# SCH_PianoBoard_P3_2024-09-13.net
KiCad netlist of a schematic drawn in EasyEDA
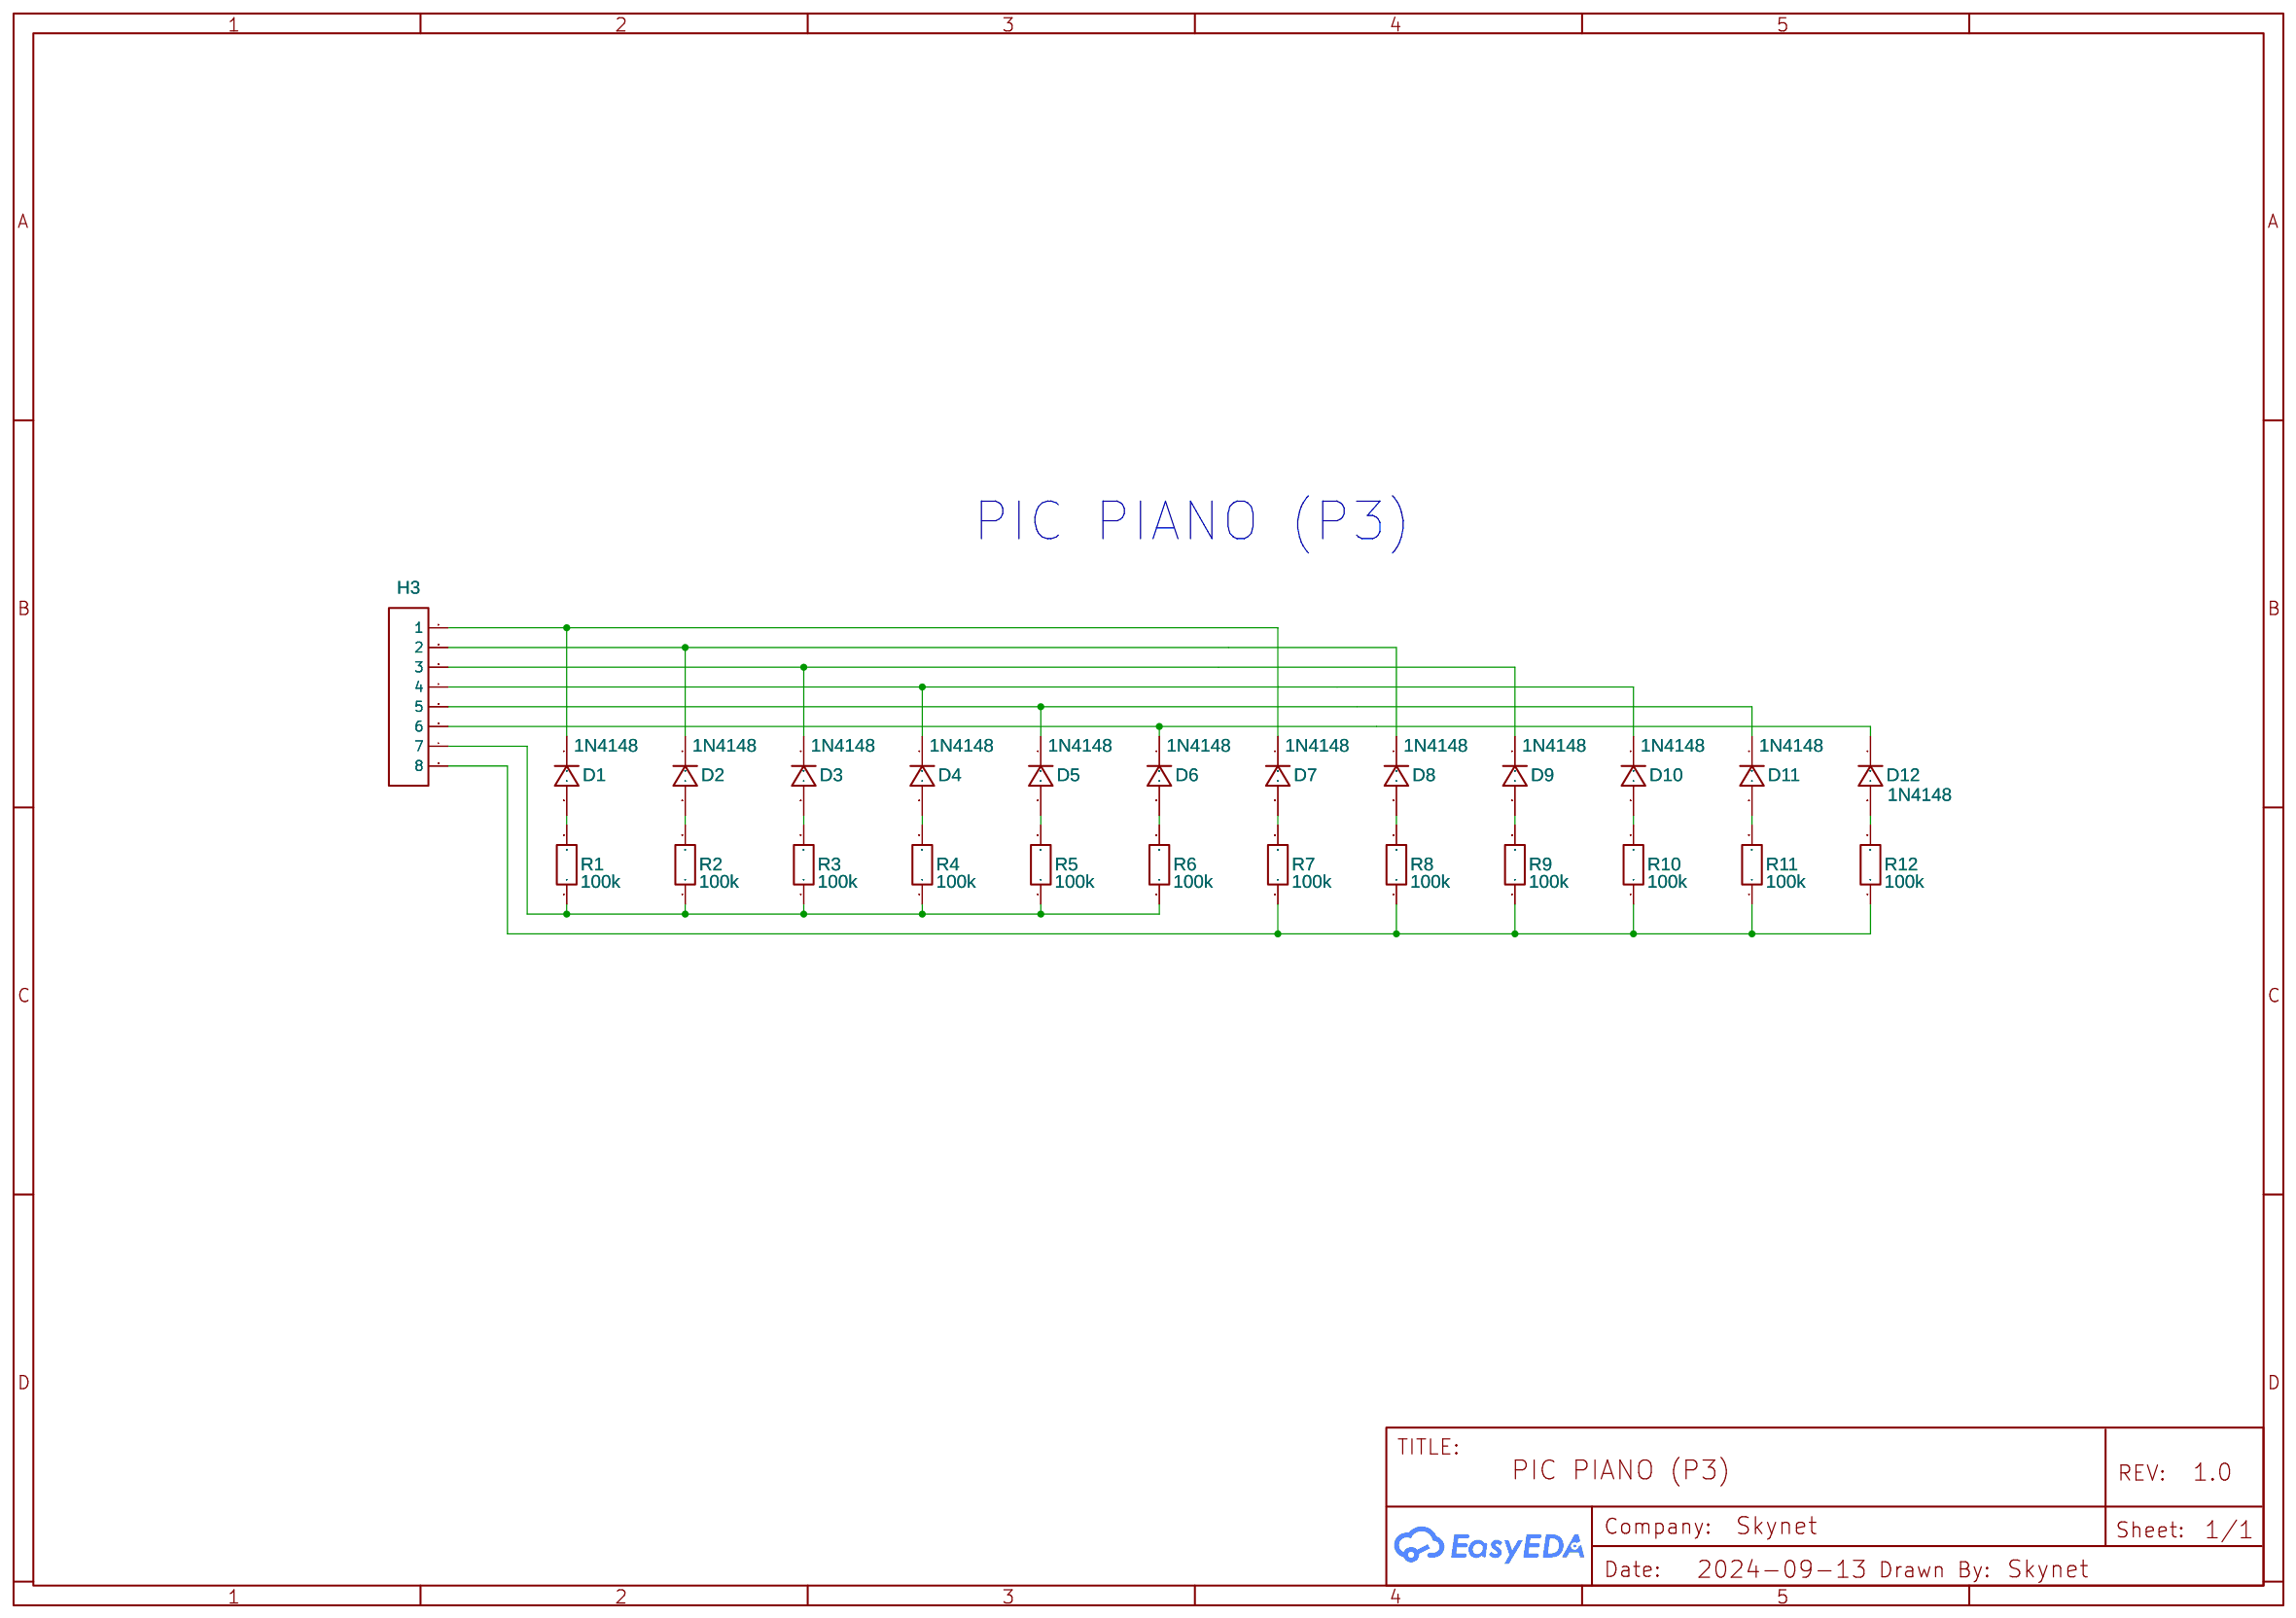
[diagram p0: schematic sheet]

(export (version "E")
  (design (tool "Eeschema 10.0.6"))
  (components
    (comp (ref "D1")
      (value "1N4148")
      (fields (field (name "Manufacturer Part") "1N4148WX-TP") (field (name "Manufacturer") "MCC(美微科)"))
      (libsource (lib "") (part "1N4148WX-TP"))
    )
    (comp (ref "D2")
      (value "1N4148")
      (fields (field (name "Manufacturer Part") "1N4148WX-TP") (field (name "Manufacturer") "MCC(美微科)"))
      (libsource (lib "") (part "1N4148WX-TP"))
    )
    (comp (ref "D3")
      (value "1N4148")
      (fields (field (name "Manufacturer Part") "1N4148WX-TP") (field (name "Manufacturer") "MCC(美微科)"))
      (libsource (lib "") (part "1N4148WX-TP"))
    )
    (comp (ref "D4")
      (value "1N4148")
      (fields (field (name "Manufacturer Part") "1N4148WX-TP") (field (name "Manufacturer") "MCC(美微科)"))
      (libsource (lib "") (part "1N4148WX-TP"))
    )
    (comp (ref "D5")
      (value "1N4148")
      (fields (field (name "Manufacturer Part") "1N4148WX-TP") (field (name "Manufacturer") "MCC(美微科)"))
      (libsource (lib "") (part "1N4148WX-TP"))
    )
    (comp (ref "D6")
      (value "1N4148")
      (fields (field (name "Manufacturer Part") "1N4148WX-TP") (field (name "Manufacturer") "MCC(美微科)"))
      (libsource (lib "") (part "1N4148WX-TP"))
    )
    (comp (ref "D7")
      (value "1N4148")
      (fields (field (name "Manufacturer Part") "1N4148WX-TP") (field (name "Manufacturer") "MCC(美微科)"))
      (libsource (lib "") (part "1N4148WX-TP"))
    )
    (comp (ref "D8")
      (value "1N4148")
      (fields (field (name "Manufacturer Part") "1N4148WX-TP") (field (name "Manufacturer") "MCC(美微科)"))
      (libsource (lib "") (part "1N4148WX-TP"))
    )
    (comp (ref "D9")
      (value "1N4148")
      (fields (field (name "Manufacturer Part") "1N4148WX-TP") (field (name "Manufacturer") "MCC(美微科)"))
      (libsource (lib "") (part "1N4148WX-TP"))
    )
    (comp (ref "D10")
      (value "1N4148")
      (fields (field (name "Manufacturer Part") "1N4148WX-TP") (field (name "Manufacturer") "MCC(美微科)"))
      (libsource (lib "") (part "1N4148WX-TP"))
    )
    (comp (ref "D11")
      (value "1N4148")
      (fields (field (name "Manufacturer Part") "1N4148WX-TP") (field (name "Manufacturer") "MCC(美微科)"))
      (libsource (lib "") (part "1N4148WX-TP"))
    )
    (comp (ref "D12")
      (value "1N4148")
      (fields (field (name "Manufacturer Part") "1N4148WX-TP") (field (name "Manufacturer") "MCC(美微科)"))
      (libsource (lib "") (part "1N4148WX-TP"))
    )
    (comp (ref "H3") (value "HDR-F-2.54_1x8") (libsource (lib "") (part "HDR-F-2.54_1x8")))
    (comp (ref "R1") (value "100k") (libsource (lib "") (part "R_0603_EU")))
    (comp (ref "R2") (value "100k") (libsource (lib "") (part "R_0603_EU")))
    (comp (ref "R3") (value "100k") (libsource (lib "") (part "R_0603_EU")))
    (comp (ref "R4") (value "100k") (libsource (lib "") (part "R_0603_EU")))
    (comp (ref "R5") (value "100k") (libsource (lib "") (part "R_0603_EU")))
    (comp (ref "R6") (value "100k") (libsource (lib "") (part "R_0603_EU")))
    (comp (ref "R7") (value "100k") (libsource (lib "") (part "R_0603_EU")))
    (comp (ref "R8") (value "100k") (libsource (lib "") (part "R_0603_EU")))
    (comp (ref "R9") (value "100k") (libsource (lib "") (part "R_0603_EU")))
    (comp (ref "R10") (value "100k") (libsource (lib "") (part "R_0603_EU")))
    (comp (ref "R11") (value "100k") (libsource (lib "") (part "R_0603_EU")))
    (comp (ref "R12") (value "100k") (libsource (lib "") (part "R_0603_EU")))
  )
  (nets
    (net (code "1") (name "Net-(D1-A)") (class "Default")
      (node (ref "D1") (pin "2") (pinfunction "A_2") (pintype "unspecified"))
      (node (ref "R1") (pin "2") (pinfunction "2_2") (pintype "unspecified"))
    )
    (net (code "2") (name "Net-(D1-C)") (class "Default")
      (node (ref "D1") (pin "1") (pinfunction "C_1") (pintype "unspecified"))
      (node (ref "D7") (pin "1") (pinfunction "C_1") (pintype "unspecified"))
      (node (ref "H3") (pin "1") (pinfunction "1_1") (pintype "unspecified"))
    )
    (net (code "3") (name "Net-(D2-A)") (class "Default")
      (node (ref "D2") (pin "2") (pinfunction "A_2") (pintype "unspecified"))
      (node (ref "R2") (pin "2") (pinfunction "2_2") (pintype "unspecified"))
    )
    (net (code "4") (name "Net-(D2-C)") (class "Default")
      (node (ref "D2") (pin "1") (pinfunction "C_1") (pintype "unspecified"))
      (node (ref "D8") (pin "1") (pinfunction "C_1") (pintype "unspecified"))
      (node (ref "H3") (pin "2") (pinfunction "2_2") (pintype "unspecified"))
    )
    (net (code "5") (name "Net-(D3-A)") (class "Default")
      (node (ref "D3") (pin "2") (pinfunction "A_2") (pintype "unspecified"))
      (node (ref "R3") (pin "2") (pinfunction "2_2") (pintype "unspecified"))
    )
    (net (code "6") (name "Net-(D3-C)") (class "Default")
      (node (ref "D3") (pin "1") (pinfunction "C_1") (pintype "unspecified"))
      (node (ref "D9") (pin "1") (pinfunction "C_1") (pintype "unspecified"))
      (node (ref "H3") (pin "3") (pinfunction "3_3") (pintype "unspecified"))
    )
    (net (code "7") (name "Net-(D4-A)") (class "Default")
      (node (ref "D4") (pin "2") (pinfunction "A_2") (pintype "unspecified"))
      (node (ref "R4") (pin "2") (pinfunction "2_2") (pintype "unspecified"))
    )
    (net (code "8") (name "Net-(D5-A)") (class "Default")
      (node (ref "D5") (pin "2") (pinfunction "A_2") (pintype "unspecified"))
      (node (ref "R5") (pin "2") (pinfunction "2_2") (pintype "unspecified"))
    )
    (net (code "9") (name "Net-(D6-A)") (class "Default")
      (node (ref "D6") (pin "2") (pinfunction "A_2") (pintype "unspecified"))
      (node (ref "R6") (pin "2") (pinfunction "2_2") (pintype "unspecified"))
    )
    (net (code "10") (name "Net-(D7-A)") (class "Default")
      (node (ref "D7") (pin "2") (pinfunction "A_2") (pintype "unspecified"))
      (node (ref "R7") (pin "2") (pinfunction "2_2") (pintype "unspecified"))
    )
    (net (code "11") (name "Net-(D8-A)") (class "Default")
      (node (ref "D8") (pin "2") (pinfunction "A_2") (pintype "unspecified"))
      (node (ref "R8") (pin "2") (pinfunction "2_2") (pintype "unspecified"))
    )
    (net (code "12") (name "Net-(D9-A)") (class "Default")
      (node (ref "D9") (pin "2") (pinfunction "A_2") (pintype "unspecified"))
      (node (ref "R9") (pin "2") (pinfunction "2_2") (pintype "unspecified"))
    )
    (net (code "13") (name "Net-(D10-A)") (class "Default")
      (node (ref "D10") (pin "2") (pinfunction "A_2") (pintype "unspecified"))
      (node (ref "R10") (pin "2") (pinfunction "2_2") (pintype "unspecified"))
    )
    (net (code "14") (name "Net-(D10-C)") (class "Default")
      (node (ref "D10") (pin "1") (pinfunction "C_1") (pintype "unspecified"))
      (node (ref "D4") (pin "1") (pinfunction "C_1") (pintype "unspecified"))
      (node (ref "H3") (pin "4") (pinfunction "4_4") (pintype "unspecified"))
    )
    (net (code "15") (name "Net-(D11-A)") (class "Default")
      (node (ref "D11") (pin "2") (pinfunction "A_2") (pintype "unspecified"))
      (node (ref "R11") (pin "2") (pinfunction "2_2") (pintype "unspecified"))
    )
    (net (code "16") (name "Net-(D11-C)") (class "Default")
      (node (ref "D11") (pin "1") (pinfunction "C_1") (pintype "unspecified"))
      (node (ref "D5") (pin "1") (pinfunction "C_1") (pintype "unspecified"))
      (node (ref "H3") (pin "5") (pinfunction "5_5") (pintype "unspecified"))
    )
    (net (code "17") (name "Net-(D12-A)") (class "Default")
      (node (ref "D12") (pin "2") (pinfunction "A_2") (pintype "unspecified"))
      (node (ref "R12") (pin "2") (pinfunction "2_2") (pintype "unspecified"))
    )
    (net (code "18") (name "Net-(D12-C)") (class "Default")
      (node (ref "D12") (pin "1") (pinfunction "C_1") (pintype "unspecified"))
      (node (ref "D6") (pin "1") (pinfunction "C_1") (pintype "unspecified"))
      (node (ref "H3") (pin "6") (pinfunction "6_6") (pintype "unspecified"))
    )
    (net (code "19") (name "Net-(H3-Pad7)") (class "Default")
      (node (ref "H3") (pin "7") (pinfunction "7_7") (pintype "unspecified"))
      (node (ref "R1") (pin "1") (pinfunction "1_1") (pintype "unspecified"))
      (node (ref "R2") (pin "1") (pinfunction "1_1") (pintype "unspecified"))
      (node (ref "R3") (pin "1") (pinfunction "1_1") (pintype "unspecified"))
      (node (ref "R4") (pin "1") (pinfunction "1_1") (pintype "unspecified"))
      (node (ref "R5") (pin "1") (pinfunction "1_1") (pintype "unspecified"))
      (node (ref "R6") (pin "1") (pinfunction "1_1") (pintype "unspecified"))
    )
    (net (code "20") (name "Net-(H3-Pad8)") (class "Default")
      (node (ref "H3") (pin "8") (pinfunction "8_8") (pintype "unspecified"))
      (node (ref "R10") (pin "1") (pinfunction "1_1") (pintype "unspecified"))
      (node (ref "R11") (pin "1") (pinfunction "1_1") (pintype "unspecified"))
      (node (ref "R12") (pin "1") (pinfunction "1_1") (pintype "unspecified"))
      (node (ref "R7") (pin "1") (pinfunction "1_1") (pintype "unspecified"))
      (node (ref "R8") (pin "1") (pinfunction "1_1") (pintype "unspecified"))
      (node (ref "R9") (pin "1") (pinfunction "1_1") (pintype "unspecified"))
    )
  )
)
